# power_supply.net
KiCad netlist of a schematic drawn in Altium Designer
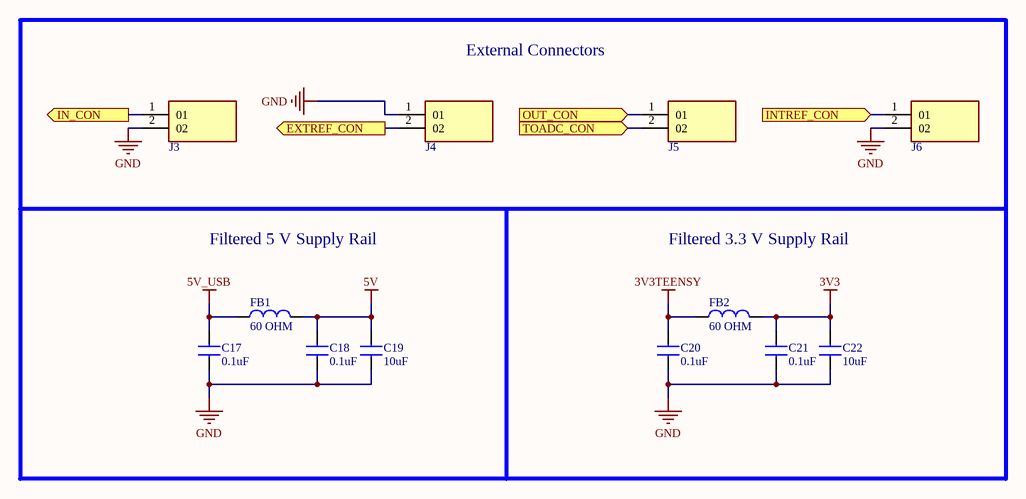
[diagram p0: power_supply.SchDoc]

(export (version "E")
  (design (tool "Eeschema 10.0.6"))
  (components
    (comp (ref "C17")
      (value "0.1uF")
      (footprint "CAP_0603")
      (description "50V 100nF Y5V -20%~+80% 0603")
      (fields (field (name "MANUFACTURER") "Walsin Tech Corp") (field (name "Comment") "CAP_100nF_50V"))
      (libsource (lib "capacitors_p") (part "CAP_100nF_50V"))
    )
    (comp (ref "C18")
      (value "0.1uF")
      (footprint "CAP_0603")
      (description "50V 100nF Y5V -20%~+80% 0603")
      (fields (field (name "MANUFACTURER") "Walsin Tech Corp") (field (name "Comment") "CAP_100nF_50V"))
      (libsource (lib "capacitors_p") (part "CAP_100nF_50V"))
    )
    (comp (ref "C19")
      (value "10uF")
      (footprint "CAP_0805")
      (description "CAP CER 10UF 25V X5R 0805 ±10%")
      (fields
        (field (name "MANUFACTURER") "Samsung Electro-Mechanics")
        (field (name "Comment") "CAP_10uF_16V")
      )
      (libsource (lib "capacitors_p") (part "CAP_10uF_16V"))
    )
    (comp (ref "C20")
      (value "0.1uF")
      (footprint "CAP_0603")
      (description "50V 100nF Y5V -20%~+80% 0603")
      (fields (field (name "MANUFACTURER") "Walsin Tech Corp") (field (name "Comment") "CAP_100nF_50V"))
      (libsource (lib "capacitors_p") (part "CAP_100nF_50V"))
    )
    (comp (ref "C21")
      (value "0.1uF")
      (footprint "CAP_0603")
      (description "50V 100nF Y5V -20%~+80% 0603")
      (fields (field (name "MANUFACTURER") "Walsin Tech Corp") (field (name "Comment") "CAP_100nF_50V"))
      (libsource (lib "capacitors_p") (part "CAP_100nF_50V"))
    )
    (comp (ref "C22")
      (value "10uF")
      (footprint "CAP_0805")
      (description "CAP CER 10UF 25V X5R 0805 ±10%")
      (fields
        (field (name "MANUFACTURER") "Samsung Electro-Mechanics")
        (field (name "Comment") "CAP_10uF_16V")
      )
      (libsource (lib "capacitors_p") (part "CAP_10uF_16V"))
    )
    (comp (ref "FB1")
      (value "60 OHM")
      (footprint "0603_FB")
      (description "2A 1 100mΩ 60Ω@100MHz ±25% 0603 Ferrite Beads ROHS")
      (fields (field (name "MANUFACTURER") "TAI-TECH") (field (name "Comment") "FB_60_0603_2A"))
      (libsource (lib "protections_p") (part "FB_60_0603_2A"))
    )
    (comp (ref "FB2")
      (value "60 OHM")
      (footprint "0603_FB")
      (description "2A 1 100mΩ 60Ω@100MHz ±25% 0603 Ferrite Beads ROHS")
      (fields (field (name "MANUFACTURER") "TAI-TECH") (field (name "Comment") "FB_60_0603_2A"))
      (libsource (lib "protections_p") (part "FB_60_0603_2A"))
    )
    (comp (ref "J3")
      (value "CON_2x1_TH_5mm")
      (footprint "CON_2x1_TH_5MM")
      (description "2POS 5MM")
      (fields (field (name "MANUFACTURER") "JILN"))
      (libsource (lib "terminal_blocks_p") (part "CON_2x1_TH_5mm"))
    )
    (comp (ref "J4")
      (value "CON_2x1_TH_5mm")
      (footprint "CON_2x1_TH_5MM")
      (description "2POS 5MM")
      (fields (field (name "MANUFACTURER") "JILN"))
      (libsource (lib "terminal_blocks_p") (part "CON_2x1_TH_5mm"))
    )
    (comp (ref "J5")
      (value "CON_2x1_TH_5mm")
      (footprint "CON_2x1_TH_5MM")
      (description "2POS 5MM")
      (fields (field (name "MANUFACTURER") "JILN"))
      (libsource (lib "terminal_blocks") (part "CON_2x1_TH_5mm"))
    )
    (comp (ref "J6")
      (value "CON_2x1_TH_5mm")
      (footprint "CON_2x1_TH_5MM")
      (description "2POS 5MM")
      (fields (field (name "MANUFACTURER") "JILN"))
      (libsource (lib "terminal_blocks_p") (part "CON_2x1_TH_5mm"))
    )
  )
  (nets
    (net (code "1") (name "/EXTREF_CON") (class "Default")
      (node (ref "J4") (pin "2") (pinfunction "02_2") (pintype "passive"))
    )
    (net (code "2") (name "/INTREF_CON") (class "Default")
      (node (ref "J6") (pin "1") (pinfunction "01_1") (pintype "passive"))
    )
    (net (code "3") (name "/IN_CON") (class "Default")
      (node (ref "J3") (pin "1") (pinfunction "01_1") (pintype "passive"))
    )
    (net (code "4") (name "/OUT_CON") (class "Default")
      (node (ref "J5") (pin "1") (pinfunction "01_1") (pintype "passive"))
    )
    (net (code "5") (name "/TOADC_CON") (class "Default")
      (node (ref "J5") (pin "2") (pinfunction "02_2") (pintype "passive"))
    )
    (net (code "6") (name "3V3") (class "Default")
      (node (ref "C21") (pin "2") (pinfunction "2_2") (pintype "passive"))
      (node (ref "C22") (pin "2") (pinfunction "2_2") (pintype "passive"))
      (node (ref "FB2") (pin "2") (pinfunction "2_2") (pintype "passive"))
    )
    (net (code "7") (name "3V3TEENSY") (class "Default")
      (node (ref "C20") (pin "2") (pinfunction "2_2") (pintype "passive"))
      (node (ref "FB2") (pin "1") (pinfunction "1_1") (pintype "passive"))
    )
    (net (code "8") (name "5V") (class "Default")
      (node (ref "C18") (pin "2") (pinfunction "2_2") (pintype "passive"))
      (node (ref "C19") (pin "2") (pinfunction "2_2") (pintype "passive"))
      (node (ref "FB1") (pin "2") (pinfunction "2_2") (pintype "passive"))
    )
    (net (code "9") (name "5V_USB") (class "Default")
      (node (ref "C17") (pin "2") (pinfunction "2_2") (pintype "passive"))
      (node (ref "FB1") (pin "1") (pinfunction "1_1") (pintype "passive"))
    )
    (net (code "10") (name "GND") (class "Default")
      (node (ref "C17") (pin "1") (pinfunction "1_1") (pintype "passive"))
      (node (ref "C18") (pin "1") (pinfunction "1_1") (pintype "passive"))
      (node (ref "C19") (pin "1") (pinfunction "1_1") (pintype "passive"))
      (node (ref "C20") (pin "1") (pinfunction "1_1") (pintype "passive"))
      (node (ref "C21") (pin "1") (pinfunction "1_1") (pintype "passive"))
      (node (ref "C22") (pin "1") (pinfunction "1_1") (pintype "passive"))
      (node (ref "J3") (pin "2") (pinfunction "02_2") (pintype "passive"))
      (node (ref "J4") (pin "1") (pinfunction "01_1") (pintype "passive"))
      (node (ref "J6") (pin "2") (pinfunction "02_2") (pintype "passive"))
    )
  )
)
